# Sheet1.net
KiCad netlist of a schematic drawn in Altium Designer
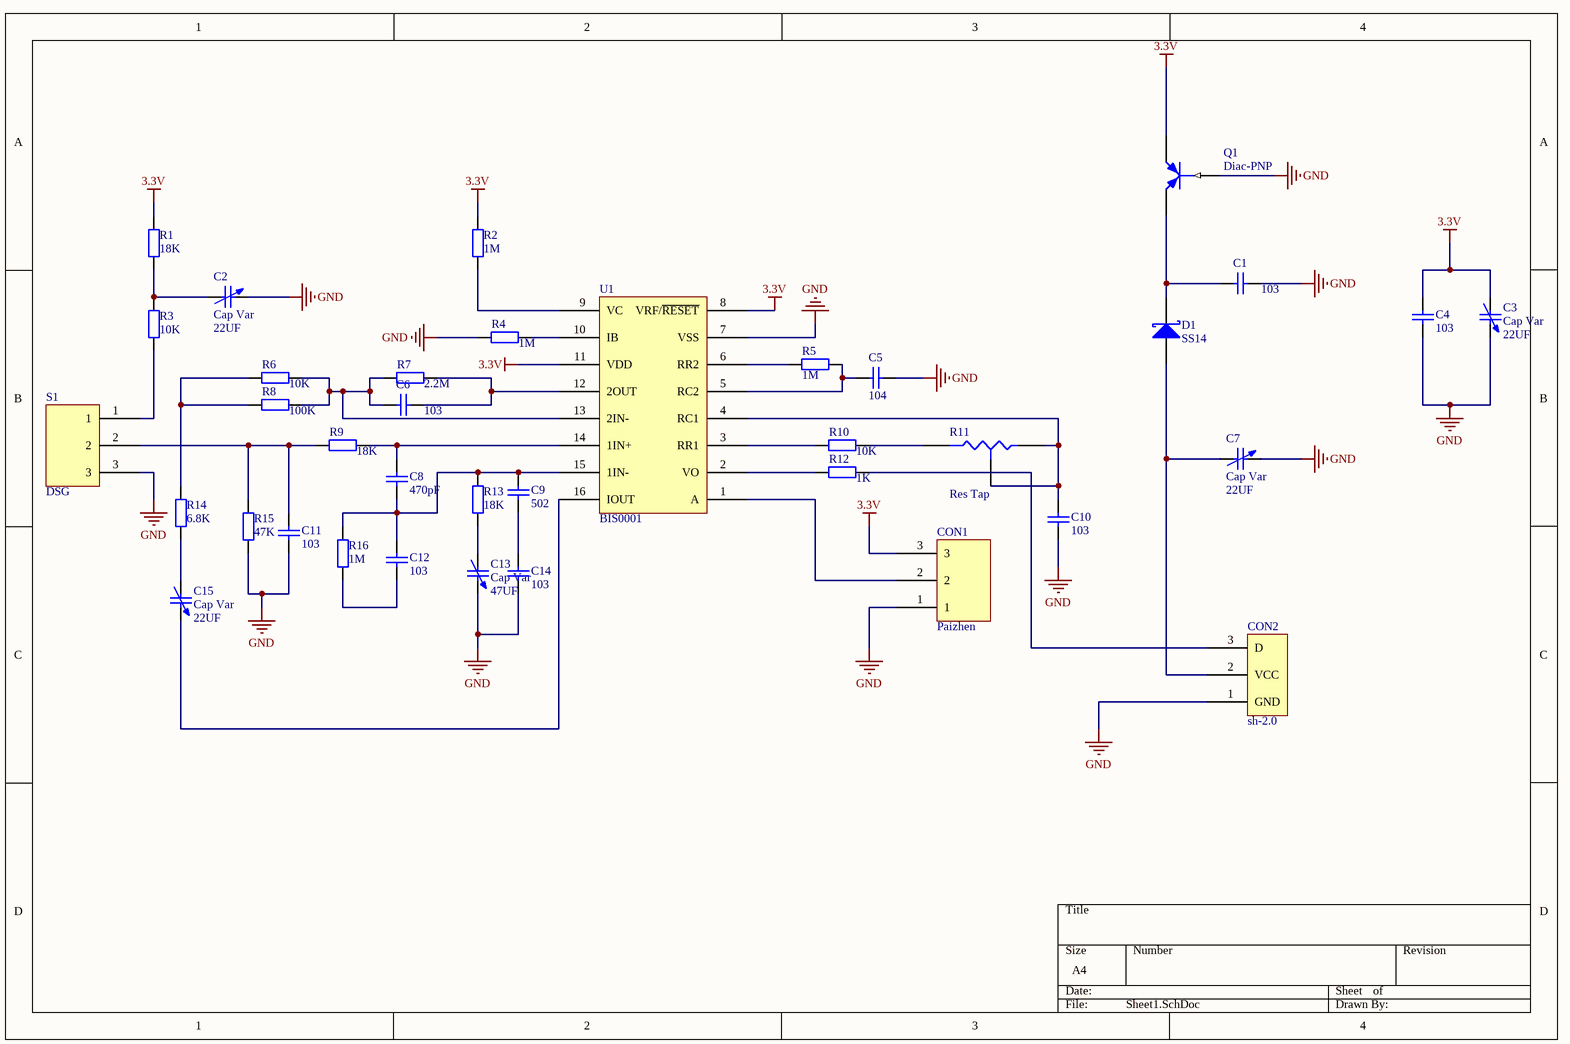
[diagram p0: Sheet1.SchDoc]

(export (version "E")
  (design (tool "Eeschema 10.0.6"))
  (components
    (comp (ref "C1")
      (value "103")
      (footprint "Miscellaneous Devices:1608[0603]")
      (description "Capacitor")
      (fields (field (name "Comment") "Cap") (field (name "PUBLISHER") "Altium Limited"))
      (libsource (lib "Miscellaneous Devices") (part "Cap"))
    )
    (comp (ref "C2")
      (value "Cap Var")
      (footprint "C1206")
      (description "Variable or Adjustable Capacitor")
      (fields (field (name "ALTIUM_VALUE") "22UF") (field (name "PUBLISHER") "Altium Limited"))
      (libsource (lib "Miscellaneous Devices") (part "Cap Var"))
    )
    (comp (ref "C3")
      (value "Cap Var")
      (footprint "C1206")
      (description "Variable or Adjustable Capacitor")
      (fields (field (name "ALTIUM_VALUE") "22UF") (field (name "PUBLISHER") "Altium Limited"))
      (libsource (lib "Miscellaneous Devices") (part "Cap Var"))
    )
    (comp (ref "C4")
      (value "103")
      (footprint "Miscellaneous Devices:1608[0603]")
      (description "Capacitor")
      (fields (field (name "Comment") "Cap") (field (name "PUBLISHER") "Altium Limited"))
      (libsource (lib "Miscellaneous Devices") (part "Cap"))
    )
    (comp (ref "C5")
      (value "104")
      (footprint "Miscellaneous Devices:1608[0603]")
      (description "Capacitor")
      (fields (field (name "Comment") "Cap") (field (name "PUBLISHER") "Altium Limited"))
      (libsource (lib "Miscellaneous Devices") (part "Cap"))
    )
    (comp (ref "C6")
      (value "103")
      (footprint "Miscellaneous Devices:1608[0603]")
      (description "Capacitor")
      (fields (field (name "Comment") "Cap") (field (name "PUBLISHER") "Altium Limited"))
      (libsource (lib "Miscellaneous Devices") (part "Cap"))
    )
    (comp (ref "C7")
      (value "Cap Var")
      (footprint "C1206")
      (description "Variable or Adjustable Capacitor")
      (fields (field (name "ALTIUM_VALUE") "22UF") (field (name "PUBLISHER") "Altium Limited"))
      (libsource (lib "Miscellaneous Devices") (part "Cap Var"))
    )
    (comp (ref "C8")
      (value "470pF")
      (footprint "Miscellaneous Devices:1608[0603]")
      (description "Capacitor")
      (fields (field (name "Comment") "Cap") (field (name "PUBLISHER") "Altium Limited"))
      (libsource (lib "Miscellaneous Devices") (part "Cap"))
    )
    (comp (ref "C9")
      (value "502")
      (footprint "Miscellaneous Devices:1608[0603]")
      (description "Capacitor")
      (fields (field (name "Comment") "Cap") (field (name "PUBLISHER") "Altium Limited"))
      (libsource (lib "Miscellaneous Devices") (part "Cap"))
    )
    (comp (ref "C10")
      (value "103")
      (footprint "Miscellaneous Devices:1608[0603]")
      (description "Capacitor")
      (fields (field (name "Comment") "Cap") (field (name "PUBLISHER") "Altium Limited"))
      (libsource (lib "Miscellaneous Devices") (part "Cap"))
    )
    (comp (ref "C11")
      (value "103")
      (footprint "Miscellaneous Devices:1608[0603]")
      (description "Capacitor")
      (fields (field (name "Comment") "Cap") (field (name "PUBLISHER") "Altium Limited"))
      (libsource (lib "Miscellaneous Devices") (part "Cap"))
    )
    (comp (ref "C12")
      (value "103")
      (footprint "Miscellaneous Devices:1608[0603]")
      (description "Capacitor")
      (fields (field (name "Comment") "Cap") (field (name "PUBLISHER") "Altium Limited"))
      (libsource (lib "Miscellaneous Devices") (part "Cap"))
    )
    (comp (ref "C13")
      (value "Cap Var")
      (footprint "C1206")
      (description "Variable or Adjustable Capacitor")
      (fields (field (name "ALTIUM_VALUE") "47UF") (field (name "PUBLISHER") "Altium Limited"))
      (libsource (lib "Miscellaneous Devices") (part "Cap Var"))
    )
    (comp (ref "C14")
      (value "103")
      (footprint "Miscellaneous Devices:1608[0603]")
      (description "Capacitor")
      (fields (field (name "Comment") "Cap") (field (name "PUBLISHER") "Altium Limited"))
      (libsource (lib "Miscellaneous Devices") (part "Cap"))
    )
    (comp (ref "C15")
      (value "Cap Var")
      (footprint "C1206")
      (description "Variable or Adjustable Capacitor")
      (fields (field (name "ALTIUM_VALUE") "22UF") (field (name "PUBLISHER") "Altium Limited"))
      (libsource (lib "Miscellaneous Devices") (part "Cap Var"))
    )
    (comp (ref "CON1")
      (value "Paizhen")
      (footprint "zhaoyujiu:Paizhen")
      (libsource (lib "zhaoyujiu") (part "Paizhen"))
    )
    (comp (ref "CON2") (value "sh-2.0") (footprint "sh-2.0") (libsource (lib "zhaoyujiu") (part "sh-2.0")))
    (comp (ref "D1")
      (value "SS14")
      (footprint "SMB")
      (description "Schottky Diode")
      (fields (field (name "PUBLISHER") "Altium Limited"))
      (libsource (lib "Miscellaneous Devices") (part "D Schottky"))
    )
    (comp (ref "Q1")
      (value "Diac-PNP")
      (footprint "SOT89L")
      (description "DIAC")
      (fields (field (name "PUBLISHER") "Altium Limited"))
      (libsource (lib "Miscellaneous Devices") (part "Diac-PNP"))
    )
    (comp (ref "R1")
      (value "18K")
      (footprint "Miscellaneous Devices:1608[0603]")
      (description "Resistor")
      (fields (field (name "Comment") "Res2") (field (name "PUBLISHER") "Altium Limited"))
      (libsource (lib "Miscellaneous Devices") (part "Res2"))
    )
    (comp (ref "R2")
      (value "1M")
      (footprint "Miscellaneous Devices:1608[0603]")
      (description "Resistor")
      (fields (field (name "Comment") "Res2") (field (name "PUBLISHER") "Altium Limited"))
      (libsource (lib "Miscellaneous Devices") (part "Res2"))
    )
    (comp (ref "R3")
      (value "10K")
      (footprint "Miscellaneous Devices:1608[0603]")
      (description "Resistor")
      (fields (field (name "Comment") "Res2") (field (name "PUBLISHER") "Altium Limited"))
      (libsource (lib "Miscellaneous Devices") (part "Res2"))
    )
    (comp (ref "R4")
      (value "1M")
      (footprint "Miscellaneous Devices:1608[0603]")
      (description "Resistor")
      (fields (field (name "Comment") "Res2") (field (name "PUBLISHER") "Altium Limited"))
      (libsource (lib "") (part "Res2_1"))
    )
    (comp (ref "R5")
      (value "1M")
      (footprint "Miscellaneous Devices:1608[0603]")
      (description "Resistor")
      (fields (field (name "Comment") "Res2") (field (name "PUBLISHER") "Altium Limited"))
      (libsource (lib "") (part "Res2_1"))
    )
    (comp (ref "R6")
      (value "10K")
      (footprint "Miscellaneous Devices:1608[0603]")
      (description "Resistor")
      (fields (field (name "Comment") "Res2") (field (name "PUBLISHER") "Altium Limited"))
      (libsource (lib "") (part "Res2_1"))
    )
    (comp (ref "R7")
      (value "2.2M")
      (footprint "Miscellaneous Devices:1608[0603]")
      (description "Resistor")
      (fields (field (name "Comment") "Res2") (field (name "PUBLISHER") "Altium Limited"))
      (libsource (lib "") (part "Res2_1"))
    )
    (comp (ref "R8")
      (value "100K")
      (footprint "Miscellaneous Devices:1608[0603]")
      (description "Resistor")
      (fields (field (name "Comment") "Res2") (field (name "PUBLISHER") "Altium Limited"))
      (libsource (lib "") (part "Res2_1"))
    )
    (comp (ref "R9")
      (value "18K")
      (footprint "Miscellaneous Devices:1608[0603]")
      (description "Resistor")
      (fields (field (name "Comment") "Res2") (field (name "PUBLISHER") "Altium Limited"))
      (libsource (lib "") (part "Res2_1"))
    )
    (comp (ref "R10")
      (value "10K")
      (footprint "Miscellaneous Devices:1608[0603]")
      (description "Resistor")
      (fields (field (name "Comment") "Res2") (field (name "PUBLISHER") "Altium Limited"))
      (libsource (lib "") (part "Res2_1"))
    )
    (comp (ref "R11")
      (value "Res Tap")
      (footprint "zhaoyujiu:R_change")
      (libsource (lib "gupeng_sch") (part "Res Tap"))
    )
    (comp (ref "R12")
      (value "1K")
      (footprint "Miscellaneous Devices:1608[0603]")
      (description "Resistor")
      (fields (field (name "Comment") "Res2") (field (name "PUBLISHER") "Altium Limited"))
      (libsource (lib "") (part "Res2_1"))
    )
    (comp (ref "R13")
      (value "18K")
      (footprint "Miscellaneous Devices:1608[0603]")
      (description "Resistor")
      (fields (field (name "Comment") "Res2") (field (name "PUBLISHER") "Altium Limited"))
      (libsource (lib "Miscellaneous Devices") (part "Res2"))
    )
    (comp (ref "R14")
      (value "6.8K")
      (footprint "Miscellaneous Devices:1608[0603]")
      (description "Resistor")
      (fields (field (name "Comment") "Res2") (field (name "PUBLISHER") "Altium Limited"))
      (libsource (lib "Miscellaneous Devices") (part "Res2"))
    )
    (comp (ref "R15")
      (value "47K")
      (footprint "Miscellaneous Devices:1608[0603]")
      (description "Resistor")
      (fields (field (name "Comment") "Res2") (field (name "PUBLISHER") "Altium Limited"))
      (libsource (lib "Miscellaneous Devices") (part "Res2"))
    )
    (comp (ref "R16")
      (value "1M")
      (footprint "Miscellaneous Devices:1608[0603]")
      (description "Resistor")
      (fields (field (name "Comment") "Res2") (field (name "PUBLISHER") "Altium Limited"))
      (libsource (lib "Miscellaneous Devices") (part "Res2"))
    )
    (comp (ref "S1") (value "DSG") (footprint "zhaoyujiu:DSG") (libsource (lib "zhaoyujiu") (part "DSG")))
    (comp (ref "U1")
      (value "BIS0001")
      (footprint "Miscellaneous Devices:SO-16_N")
      (libsource (lib "zhaoyujiu") (part "BISS0001"))
    )
  )
  (nets
    (net (code "1") (name "3.3V") (class "Default")
      (node (ref "C3") (pin "1") (pinfunction "1_1") (pintype "passive"))
      (node (ref "C4") (pin "2") (pinfunction "2_2") (pintype "passive"))
      (node (ref "CON1") (pin "3") (pinfunction "3_3") (pintype "passive"))
      (node (ref "Q1") (pin "3") (pinfunction "C_3") (pintype "passive"))
      (node (ref "R1") (pin "1") (pinfunction "1_1") (pintype "passive"))
      (node (ref "R2") (pin "1") (pinfunction "1_1") (pintype "passive"))
      (node (ref "U1") (pin "11") (pinfunction "VDD_11") (pintype "passive"))
      (node (ref "U1") (pin "8") (pinfunction "VRF/~{RESET}_8") (pintype "passive"))
    )
    (net (code "2") (name "GND") (class "Default")
      (node (ref "C1") (pin "2") (pinfunction "2_2") (pintype "passive"))
      (node (ref "C10") (pin "1") (pinfunction "1_1") (pintype "passive"))
      (node (ref "C11") (pin "1") (pinfunction "1_1") (pintype "passive"))
      (node (ref "C13") (pin "2") (pinfunction "2_2") (pintype "passive"))
      (node (ref "C14") (pin "1") (pinfunction "1_1") (pintype "passive"))
      (node (ref "C2") (pin "2") (pinfunction "2_2") (pintype "passive"))
      (node (ref "C3") (pin "2") (pinfunction "2_2") (pintype "passive"))
      (node (ref "C4") (pin "1") (pinfunction "1_1") (pintype "passive"))
      (node (ref "C5") (pin "1") (pinfunction "1_1") (pintype "passive"))
      (node (ref "C7") (pin "2") (pinfunction "2_2") (pintype "passive"))
      (node (ref "CON1") (pin "1") (pinfunction "1_1") (pintype "passive"))
      (node (ref "CON2") (pin "1") (pinfunction "GND_1") (pintype "passive"))
      (node (ref "Q1") (pin "1") (pinfunction "B_1") (pintype "input"))
      (node (ref "R15") (pin "2") (pinfunction "2_2") (pintype "passive"))
      (node (ref "R4") (pin "2") (pinfunction "2_2") (pintype "passive"))
      (node (ref "S1") (pin "3") (pinfunction "3_3") (pintype "passive"))
      (node (ref "U1") (pin "7") (pinfunction "VSS_7") (pintype "passive"))
    )
    (net (code "3") (name "Net-(C2-Pad1)") (class "Default")
      (node (ref "C2") (pin "1") (pinfunction "1_1") (pintype "passive"))
      (node (ref "R1") (pin "2") (pinfunction "2_2") (pintype "passive"))
      (node (ref "R3") (pin "1") (pinfunction "1_1") (pintype "passive"))
    )
    (net (code "4") (name "Net-(C11-Pad2)") (class "Default")
      (node (ref "C11") (pin "2") (pinfunction "2_2") (pintype "passive"))
      (node (ref "R15") (pin "1") (pinfunction "1_1") (pintype "passive"))
      (node (ref "R9") (pin "2") (pinfunction "2_2") (pintype "passive"))
      (node (ref "S1") (pin "2") (pinfunction "2_2") (pintype "passive"))
    )
    (net (code "5") (name "Net-(C12-Pad1)") (class "Default")
      (node (ref "C12") (pin "1") (pinfunction "1_1") (pintype "passive"))
      (node (ref "R16") (pin "2") (pinfunction "2_2") (pintype "passive"))
    )
    (net (code "6") (name "Net-(C13-Pad1)") (class "Default")
      (node (ref "C13") (pin "1") (pinfunction "1_1") (pintype "passive"))
      (node (ref "R13") (pin "2") (pinfunction "2_2") (pintype "passive"))
    )
    (net (code "7") (name "Net-(C14-Pad2)") (class "Default")
      (node (ref "C14") (pin "2") (pinfunction "2_2") (pintype "passive"))
      (node (ref "C9") (pin "1") (pinfunction "1_1") (pintype "passive"))
    )
    (net (code "8") (name "Net-(C15-Pad1)") (class "Default")
      (node (ref "C15") (pin "1") (pinfunction "1_1") (pintype "passive"))
      (node (ref "R14") (pin "2") (pinfunction "2_2") (pintype "passive"))
    )
    (net (code "9") (name "Net-(CON2-D)") (class "Default")
      (node (ref "CON2") (pin "3") (pinfunction "D_3") (pintype "passive"))
      (node (ref "R12") (pin "1") (pinfunction "1_1") (pintype "passive"))
    )
    (net (code "10") (name "Net-(CON2-VCC)") (class "Default")
      (node (ref "C7") (pin "1") (pinfunction "1_1") (pintype "passive"))
      (node (ref "CON2") (pin "2") (pinfunction "VCC_2") (pintype "passive"))
      (node (ref "D1") (pin "1") (pinfunction "A_1") (pintype "passive"))
    )
    (net (code "11") (name "Net-(D1-K)") (class "Default")
      (node (ref "C1") (pin "1") (pinfunction "1_1") (pintype "passive"))
      (node (ref "D1") (pin "2") (pinfunction "K_2") (pintype "passive"))
      (node (ref "Q1") (pin "2") (pinfunction "E_2") (pintype "passive"))
    )
    (net (code "12") (name "Net-(R3-Pad2)") (class "Default")
      (node (ref "R3") (pin "2") (pinfunction "2_2") (pintype "passive"))
      (node (ref "S1") (pin "1") (pinfunction "1_1") (pintype "passive"))
    )
    (net (code "13") (name "Net-(R11-A)") (class "Default")
      (node (ref "C10") (pin "2") (pinfunction "2_2") (pintype "passive"))
      (node (ref "R11") (pin "1") (pinfunction "A_1") (pintype "passive"))
      (node (ref "R11") (pin "3") (pinfunction "TAP_3") (pintype "passive"))
      (node (ref "U1") (pin "4") (pinfunction "RC1_4") (pintype "passive"))
    )
    (net (code "14") (name "Net-(R11-B)") (class "Default")
      (node (ref "R10") (pin "1") (pinfunction "1_1") (pintype "passive"))
      (node (ref "R11") (pin "2") (pinfunction "B_2") (pintype "passive"))
    )
    (net (code "15") (name "Net-(R14-Pad1)") (class "Default")
      (node (ref "R14") (pin "1") (pinfunction "1_1") (pintype "passive"))
      (node (ref "R6") (pin "2") (pinfunction "2_2") (pintype "passive"))
      (node (ref "R8") (pin "2") (pinfunction "2_2") (pintype "passive"))
    )
    (net (code "16") (name "Net-(U1-1IN+)") (class "Default")
      (node (ref "C8") (pin "2") (pinfunction "2_2") (pintype "passive"))
      (node (ref "R9") (pin "1") (pinfunction "1_1") (pintype "passive"))
      (node (ref "U1") (pin "14") (pinfunction "1IN+_14") (pintype "passive"))
    )
    (net (code "17") (name "Net-(U1-1IN-)") (class "Default")
      (node (ref "C12") (pin "2") (pinfunction "2_2") (pintype "passive"))
      (node (ref "C8") (pin "1") (pinfunction "1_1") (pintype "passive"))
      (node (ref "C9") (pin "2") (pinfunction "2_2") (pintype "passive"))
      (node (ref "R13") (pin "1") (pinfunction "1_1") (pintype "passive"))
      (node (ref "R16") (pin "1") (pinfunction "1_1") (pintype "passive"))
      (node (ref "U1") (pin "15") (pinfunction "1IN-_15") (pintype "passive"))
    )
    (net (code "18") (name "Net-(U1-2IN-)") (class "Default")
      (node (ref "C6") (pin "1") (pinfunction "1_1") (pintype "passive"))
      (node (ref "R6") (pin "1") (pinfunction "1_1") (pintype "passive"))
      (node (ref "R7") (pin "2") (pinfunction "2_2") (pintype "passive"))
      (node (ref "R8") (pin "1") (pinfunction "1_1") (pintype "passive"))
      (node (ref "U1") (pin "13") (pinfunction "2IN-_13") (pintype "passive"))
    )
    (net (code "19") (name "Net-(U1-2OUT)") (class "Default")
      (node (ref "C6") (pin "2") (pinfunction "2_2") (pintype "passive"))
      (node (ref "R7") (pin "1") (pinfunction "1_1") (pintype "passive"))
      (node (ref "U1") (pin "12") (pinfunction "2OUT_12") (pintype "passive"))
    )
    (net (code "20") (name "Net-(U1-A)") (class "Default")
      (node (ref "CON1") (pin "2") (pinfunction "2_2") (pintype "passive"))
      (node (ref "U1") (pin "1") (pinfunction "A_1") (pintype "passive"))
    )
    (net (code "21") (name "Net-(U1-IB)") (class "Default")
      (node (ref "R4") (pin "1") (pinfunction "1_1") (pintype "passive"))
      (node (ref "U1") (pin "10") (pinfunction "IB_10") (pintype "passive"))
    )
    (net (code "22") (name "Net-(U1-IOUT)") (class "Default")
      (node (ref "C15") (pin "2") (pinfunction "2_2") (pintype "passive"))
      (node (ref "U1") (pin "16") (pinfunction "IOUT_16") (pintype "passive"))
    )
    (net (code "23") (name "Net-(U1-RC2)") (class "Default")
      (node (ref "C5") (pin "2") (pinfunction "2_2") (pintype "passive"))
      (node (ref "R5") (pin "1") (pinfunction "1_1") (pintype "passive"))
      (node (ref "U1") (pin "5") (pinfunction "RC2_5") (pintype "passive"))
    )
    (net (code "24") (name "Net-(U1-RR1)") (class "Default")
      (node (ref "R10") (pin "2") (pinfunction "2_2") (pintype "passive"))
      (node (ref "U1") (pin "3") (pinfunction "RR1_3") (pintype "passive"))
    )
    (net (code "25") (name "Net-(U1-RR2)") (class "Default")
      (node (ref "R5") (pin "2") (pinfunction "2_2") (pintype "passive"))
      (node (ref "U1") (pin "6") (pinfunction "RR2_6") (pintype "passive"))
    )
    (net (code "26") (name "Net-(U1-VC)") (class "Default")
      (node (ref "R2") (pin "2") (pinfunction "2_2") (pintype "passive"))
      (node (ref "U1") (pin "9") (pinfunction "VC_9") (pintype "passive"))
    )
    (net (code "27") (name "Net-(U1-VO)") (class "Default")
      (node (ref "R12") (pin "2") (pinfunction "2_2") (pintype "passive"))
      (node (ref "U1") (pin "2") (pinfunction "VO_2") (pintype "passive"))
    )
  )
)
